# Thermostat_Power_Supply.net
KiCad netlist of a schematic drawn in Altium Designer
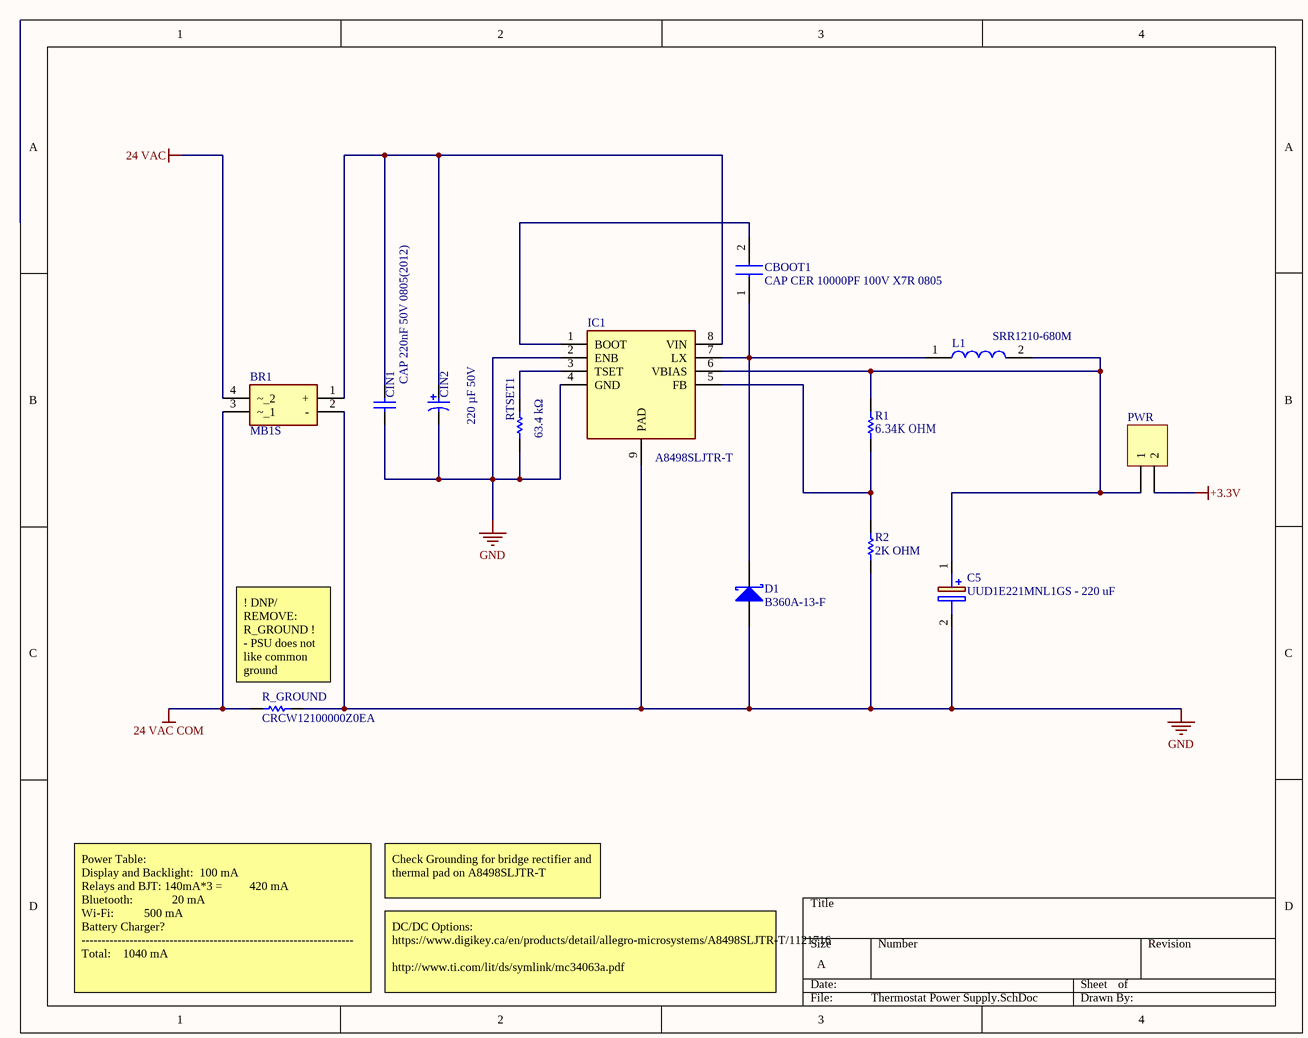
[diagram p0: Thermostat Power Supply.SchDoc]

(export (version "E")
  (design (tool "Eeschema 10.0.6"))
  (components
    (comp (ref "BR1")
      (value "MB1S")
      (footprint "SamacSys:SOP245P670X290-4N")
      (description "Bridge Rectifier")
      (fields (field (name "MOUSER PART NUMBER") "512-MB1S"))
      (libsource (lib "*") (part "MB1S"))
    )
    (comp (ref "C5")
      (value "UUD1E221MNL1GS - 220 uF")
      (footprint "SamacSys:CAPAE830X1050N")
      (description "Capacitor Polarised")
      (fields
        (field (name "MANUFACTURER_PART_NUMBER") "UUD1E221MNL1GS")
        (field (name "MOUSER PART NUMBER") "647-UUD1E221MNL")
      )
      (libsource (lib "*") (part "UUD1E221MNL1GS"))
    )
    (comp (ref "CBOOT1")
      (value "CAP CER 10000PF 100V X7R 0805")
      (footprint "SamacSys:CAPC2012X88N")
      (description "Capacitor")
      (fields
        (field (name "MANUFACTURER_PART_NUMBER") "C0805C103K1RACTU")
        (field (name "MOUSER PART NUMBER") "80-C0805C103K1R")
      )
      (libsource (lib "*") (part "C0805C103K1RACTU"))
    )
    (comp (ref "CIN1")
      (value "CAP 220nF 50V 0805(2012)")
      (footprint "CAPC0805(2012)145_N")
      (description "CAP 220nF 50V ±10% 0805 (2012 Metric) Thickness 1.45mm SMD")
      (fields (field (name "TOLERANCE") "Â±10%"))
      (libsource (lib "Altium Content Vault") (part "CAP"))
    )
    (comp (ref "CIN2")
      (value "220 µF 50V")
      (footprint "NIC-CAPA2-10X10_V")
      (fields (field (name "PARTNUMBER") "UUD1H221MNL1GS") (field (name "MANUFACTURER") "Nichicon"))
      (libsource (lib "Altium Content Vault") (part "NIC-CAP-P-2"))
    )
    (comp (ref "D1")
      (value "B360A-13-F")
      (footprint "DIOD-B360A_V")
      (description "Schottky Barrier Rectifier, 3 A, -55 to 150 degC, 2-Pin Molded, RoHS, Tape and Reel")
      (fields (field (name "MANUFACTURER") "DiodesIncorporated"))
      (libsource (lib "Altium Content Vault") (part "DSKY-AK-2"))
    )
    (comp (ref "IC1")
      (value "A8498SLJTR-T")
      (footprint "SamacSys:SOIC127P600X170-9N")
      (description "Integrated Circuit")
      (libsource (lib "*") (part "A8498SLJTR-T"))
    )
    (comp (ref "L1")
      (value "SRR1210-680M")
      (footprint "SamacSys:SRR1210")
      (description "Inductor")
      (fields (field (name "MOUSER PART NUMBER") "652-SRR1210-680M"))
      (libsource (lib "*") (part "SRR1210-680M"))
    )
    (comp (ref "PWR")
      (value "Header 2")
      (footprint "HDR1X2")
      (description "Header, 2-Pin")
      (fields (field (name "PUBLISHER") "Altium Limited"))
      (libsource (lib "Miscellaneous Connectors") (part "Header 2"))
    )
    (comp (ref "R1")
      (value "‎6.34K OHM ‎")
      (footprint "RESC2013X60X35NL10T20")
      (description "RES 6.34K OHM")
      (fields (field (name "MANUFACTURER") "Yageo") (field (name "PART NUMBER") "RC0805FR-076R34L"))
      (libsource (lib "Altium Content Vault") (part "RES"))
    )
    (comp (ref "R2")
      (value "2K OHM")
      (footprint "RESC2013X60X35ML10T20")
      (fields (field (name "MANUFACTURER") "Yageo") (field (name "PART NUMBER") "RC0805JR-072KL"))
      (libsource (lib "Altium Content Vault") (part "RES"))
    )
    (comp (ref "RTSET1")
      (value "63.4 kΩ")
      (footprint "RESC2013X60X40NL20T25")
      (fields (field (name "MANUFACTURER") "Panasonic") (field (name "PART NUMBER") "ERA6AEB6342V"))
      (libsource (lib "Altium Content Vault") (part "RES"))
    )
    (comp (ref "R_GROUND")
      (value "CRCW12100000Z0EA")
      (footprint "RESC3225X60X45NL20T20")
      (fields (field (name "MANUFACTURER") "Vishay Dale"))
      (libsource (lib "Altium Content Vault") (part "RES"))
    )
  )
  (nets
    (net (code "1") (name "+3.3V") (class "Default")
      (node (ref "PWR") (pin "2") (pinfunction "2_2") (pintype "passive"))
    )
    (net (code "2") (name "24 VAC") (class "Default")
      (node (ref "BR1") (pin "4") (pinfunction "~_2_4") (pintype "passive"))
    )
    (net (code "3") (name "24 VAC COM") (class "Default")
      (node (ref "BR1") (pin "3") (pinfunction "~_1_3") (pintype "passive"))
      (node (ref "R_GROUND") (pin "1") (pinfunction "1_1") (pintype "passive"))
    )
    (net (code "4") (name "GND") (class "Default")
      (node (ref "BR1") (pin "2") (pinfunction "-_2") (pintype "passive"))
      (node (ref "C5") (pin "2") (pinfunction "-_2") (pintype "passive"))
      (node (ref "CIN1") (pin "1") (pinfunction "1_1") (pintype "passive"))
      (node (ref "CIN2") (pin "2") (pinfunction "2_2") (pintype "passive"))
      (node (ref "D1") (pin "1") (pinfunction "A_1") (pintype "passive"))
      (node (ref "IC1") (pin "2") (pinfunction "ENB_2") (pintype "passive"))
      (node (ref "IC1") (pin "4") (pinfunction "GND_4") (pintype "passive"))
      (node (ref "IC1") (pin "9") (pinfunction "PAD_9") (pintype "passive"))
      (node (ref "R2") (pin "1") (pinfunction "1_1") (pintype "passive"))
      (node (ref "RTSET1") (pin "1") (pinfunction "1_1") (pintype "passive"))
      (node (ref "R_GROUND") (pin "2") (pinfunction "2_2") (pintype "passive"))
    )
    (net (code "5") (name "Net-(BR1-+)") (class "Default")
      (node (ref "BR1") (pin "1") (pinfunction "+_1") (pintype "passive"))
      (node (ref "CIN1") (pin "2") (pinfunction "2_2") (pintype "passive"))
      (node (ref "CIN2") (pin "1") (pinfunction "1_1") (pintype "passive"))
      (node (ref "IC1") (pin "8") (pinfunction "VIN_8") (pintype "passive"))
    )
    (net (code "6") (name "Net-(C5-+)") (class "Default")
      (node (ref "C5") (pin "1") (pinfunction "+_1") (pintype "passive"))
      (node (ref "IC1") (pin "6") (pinfunction "VBIAS_6") (pintype "passive"))
      (node (ref "L1") (pin "2") (pinfunction "2_2") (pintype "passive"))
      (node (ref "PWR") (pin "1") (pinfunction "1_1") (pintype "passive"))
      (node (ref "R1") (pin "2") (pinfunction "2_2") (pintype "passive"))
    )
    (net (code "7") (name "Net-(D1-K)") (class "Default")
      (node (ref "CBOOT1") (pin "1") (pinfunction "1_1") (pintype "passive"))
      (node (ref "D1") (pin "2") (pinfunction "K_2") (pintype "passive"))
      (node (ref "IC1") (pin "7") (pinfunction "LX_7") (pintype "passive"))
      (node (ref "L1") (pin "1") (pinfunction "1_1") (pintype "passive"))
    )
    (net (code "8") (name "Net-(IC1-BOOT)") (class "Default")
      (node (ref "CBOOT1") (pin "2") (pinfunction "2_2") (pintype "passive"))
      (node (ref "IC1") (pin "1") (pinfunction "BOOT_1") (pintype "passive"))
    )
    (net (code "9") (name "Net-(IC1-FB)") (class "Default")
      (node (ref "IC1") (pin "5") (pinfunction "FB_5") (pintype "passive"))
      (node (ref "R1") (pin "1") (pinfunction "1_1") (pintype "passive"))
      (node (ref "R2") (pin "2") (pinfunction "2_2") (pintype "passive"))
    )
    (net (code "10") (name "Net-(IC1-TSET)") (class "Default")
      (node (ref "IC1") (pin "3") (pinfunction "TSET_3") (pintype "passive"))
      (node (ref "RTSET1") (pin "2") (pinfunction "2_2") (pintype "passive"))
    )
  )
)
